# SCH_ShieldV1_1_sch_2022-06-14.net
KiCad netlist of a schematic drawn in EasyEDA
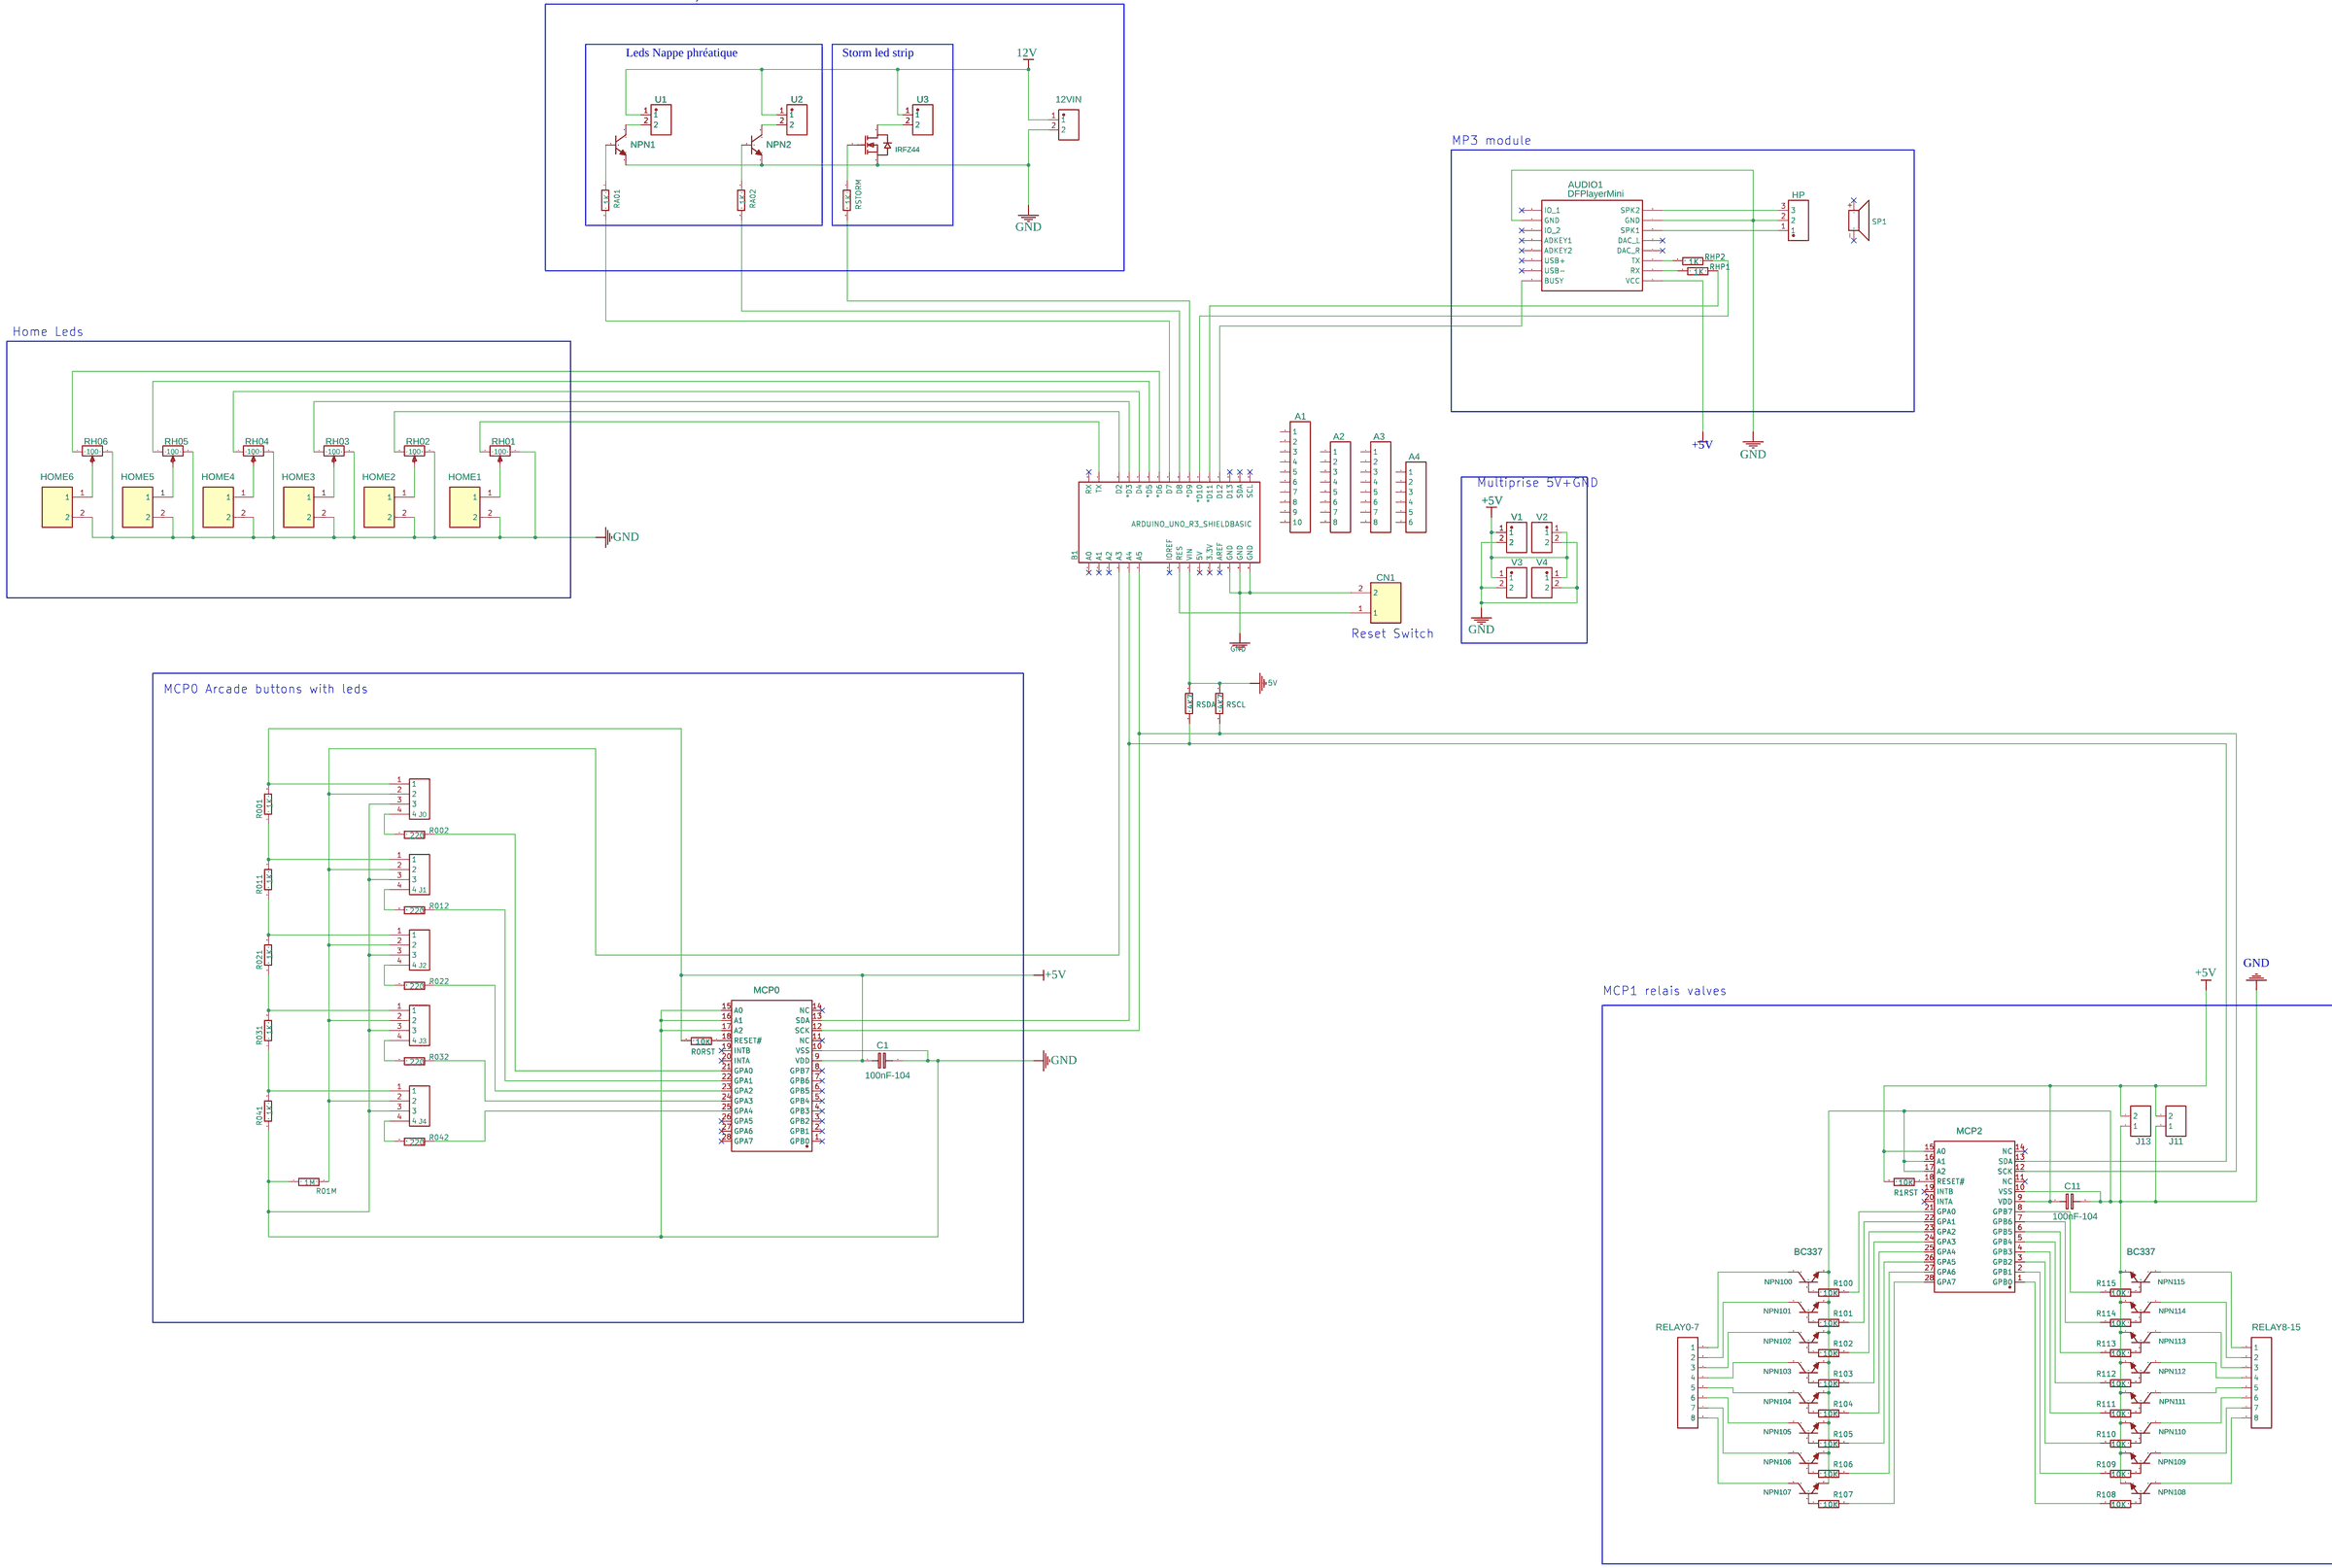
[diagram p0: Main board]
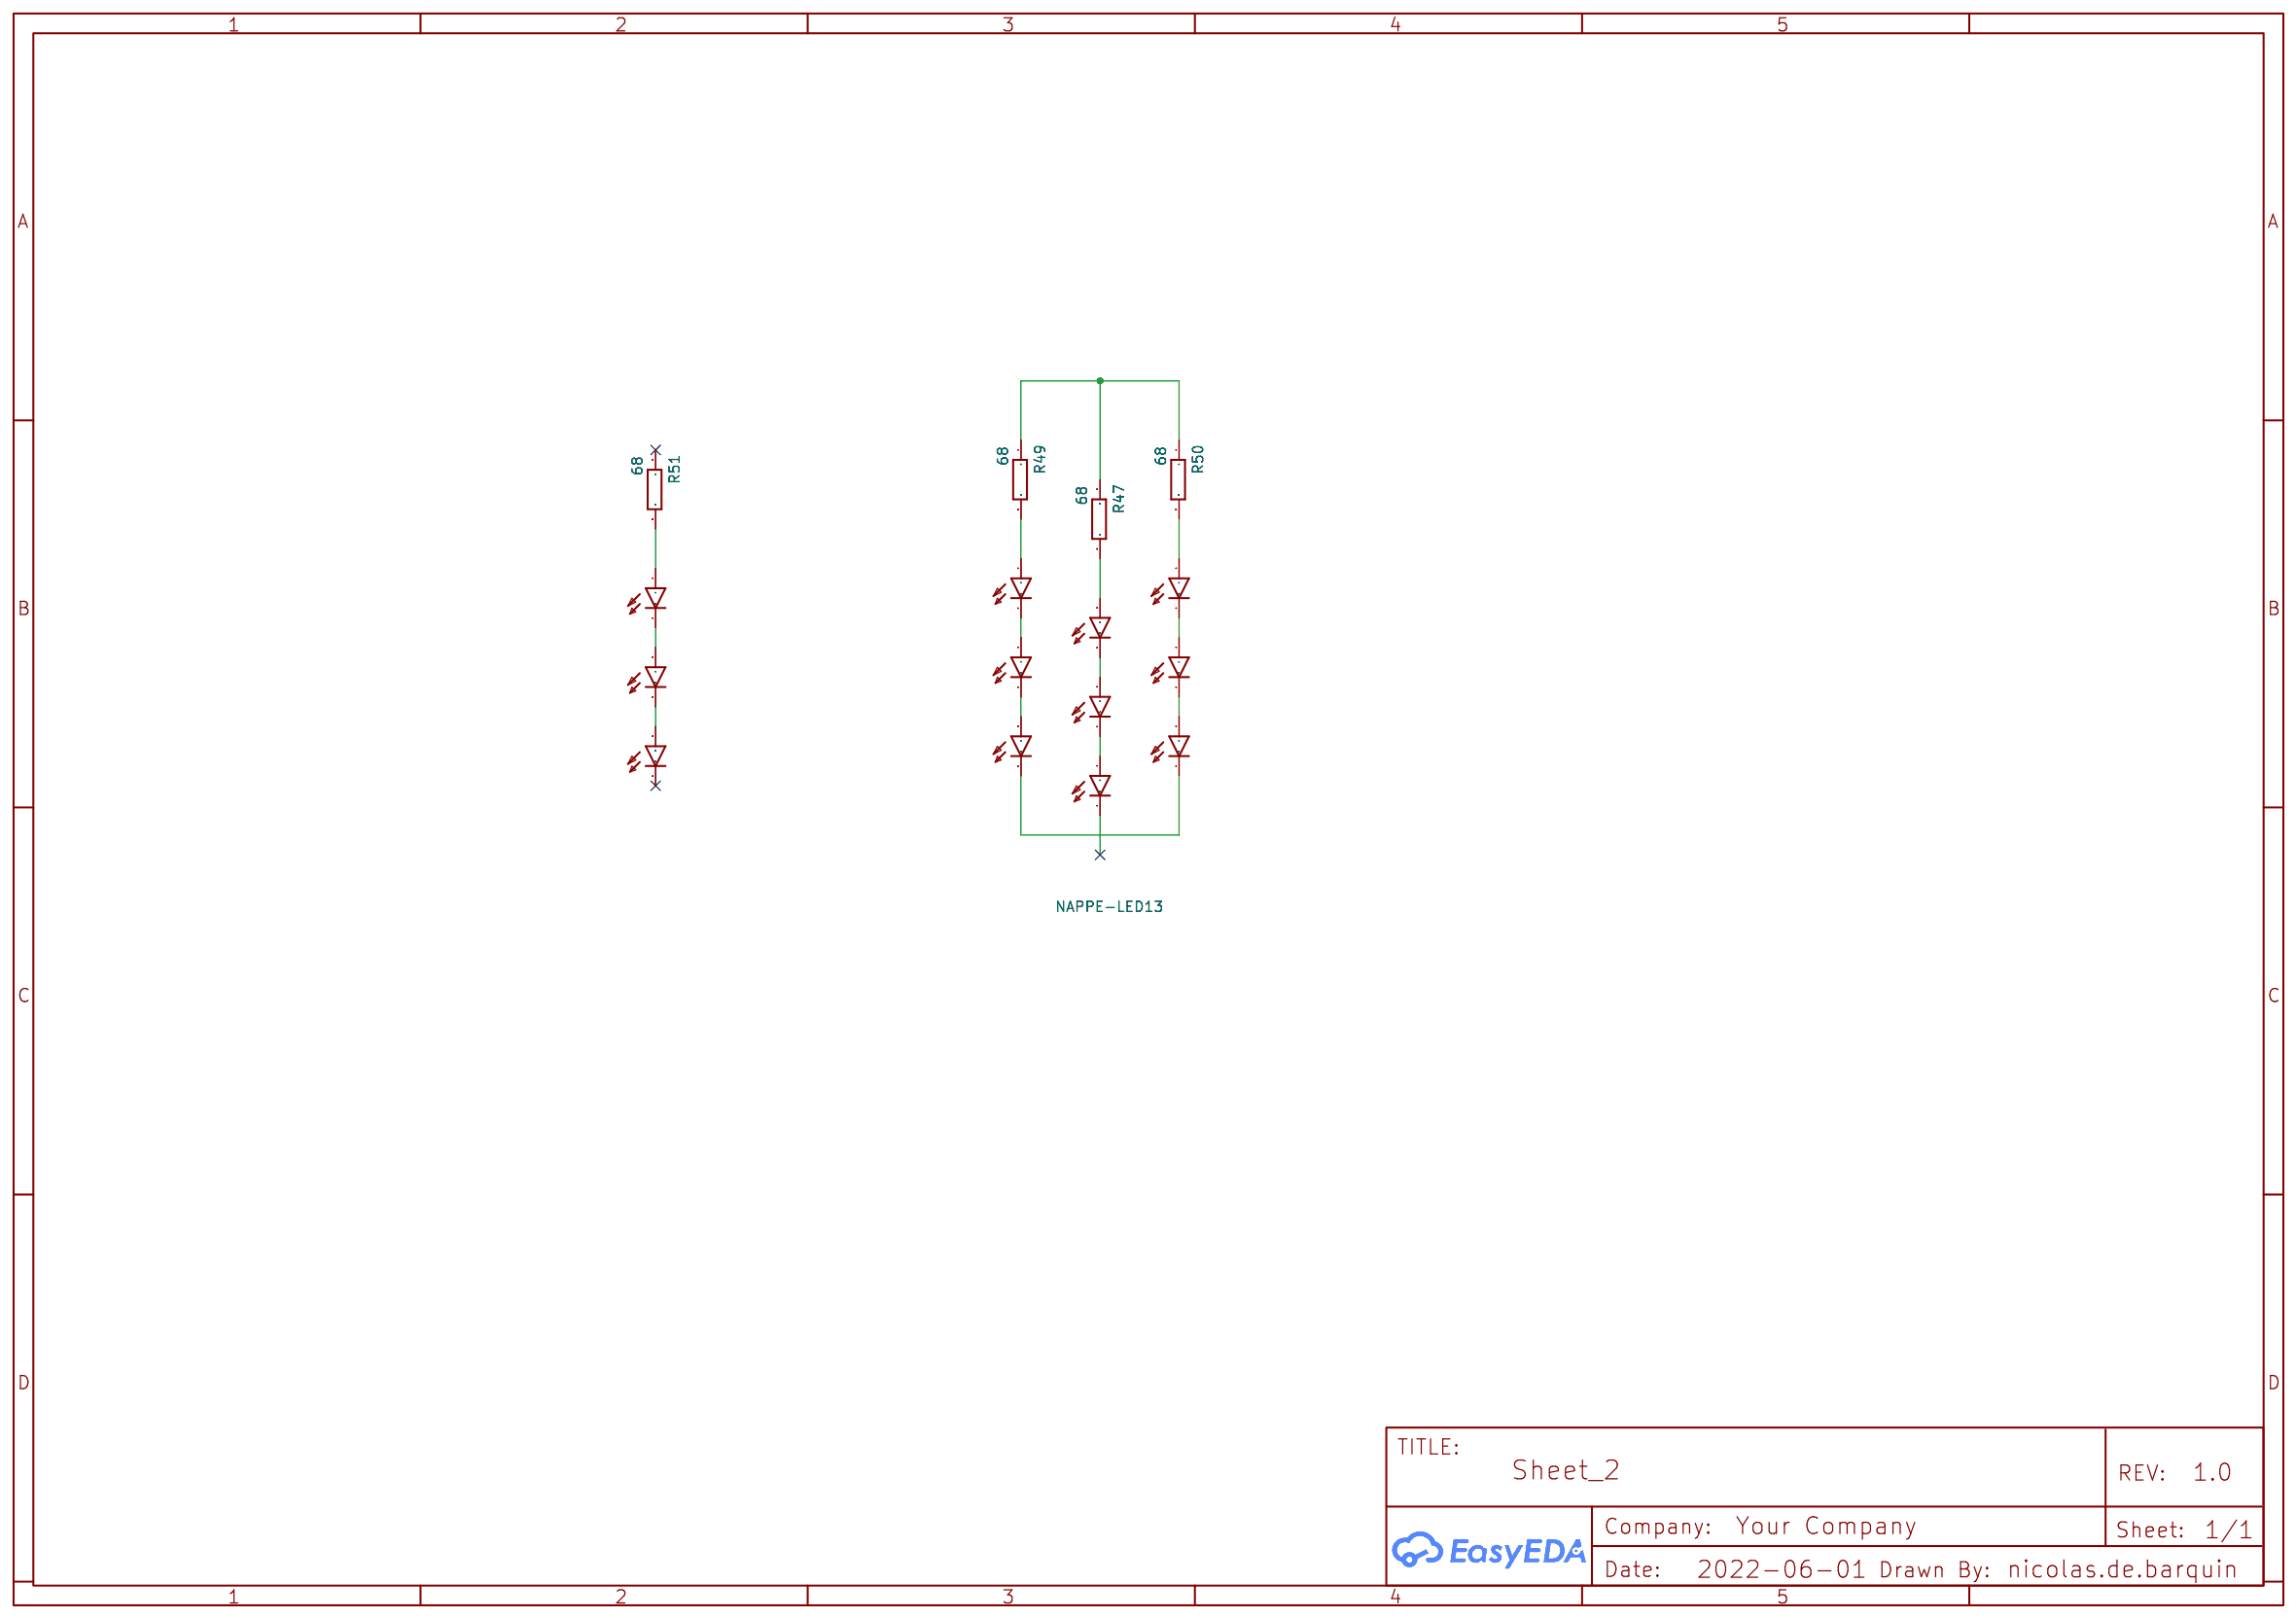
[diagram p1: leds]

(export (version "E")
  (design (tool "Eeschema 10.0.6"))
  (components
    (comp (ref "12VIN")
      (value "12V IN")
      (fields
        (field (name "BOM_Manufacturer Part") "KF301-5.0-2P")
        (field (name "BOM_Supplier Part") "C474881")
      )
      (libsource (lib "") (part "KF301-5.0-2P_3"))
    )
    (comp (ref "A1")
      (value "HDR-M-2.54_1x10")
      (fields (field (name "BOM_Supplier Part") "C57369"))
      (libsource (lib "") (part "HDR-M-2.54_1x10"))
    )
    (comp (ref "A2")
      (value "HDR-M-2.54_1x8")
      (fields (field (name "BOM_Supplier Part") "C190820"))
      (libsource (lib "") (part "HDR-M-2.54_1x8"))
    )
    (comp (ref "A3")
      (value "HDR-M-2.54_1x8")
      (fields (field (name "BOM_Supplier Part") "C190820"))
      (libsource (lib "") (part "HDR-M-2.54_1x8"))
    )
    (comp (ref "A4")
      (value "HDR-M-2.54_1x6")
      (fields (field (name "BOM_Supplier Part") "C190819"))
      (libsource (lib "") (part "HDR-M-2.54_1x6"))
    )
    (comp (ref "AUDIO1")
      (value "DFPlayerMini")
      (fields (field (name "BOM_Manufacturer Part") "DFPlayer mini"))
      (libsource (lib "") (part "DFPlayerMini"))
    )
    (comp (ref "B1") (value "ARDUINO_UNO_R3_SHIELDBASIC") (libsource (lib "") (part "Unknown_1660_-1370")))
    (comp (ref "C1") (value "100nF-104") (libsource (lib "") (part "C_RAD-0.1_EU")))
    (comp (ref "C11") (value "100nF-104") (libsource (lib "") (part "C_RAD-0.1_EU_1")))
    (comp (ref "CN1")
      (value "B2B-PH-K-S(LF)(SN)")
      (fields (field (name "BOM_Supplier Part") "C131337"))
      (libsource (lib "") (part "B2B-PH-K-S(LF)(SN)_1"))
    )
    (comp (ref "HOME1")
      (value "B2B-PH-K-S(LF)(SN)")
      (fields (field (name "BOM_Supplier Part") "C131337"))
      (libsource (lib "") (part "B2B-PH-K-S(LF)(SN)"))
    )
    (comp (ref "HOME2")
      (value "B2B-PH-K-S(LF)(SN)")
      (fields (field (name "BOM_Supplier Part") "C131337"))
      (libsource (lib "") (part "B2B-PH-K-S(LF)(SN)"))
    )
    (comp (ref "HOME3")
      (value "B2B-PH-K-S(LF)(SN)")
      (fields (field (name "BOM_Supplier Part") "C131337"))
      (libsource (lib "") (part "B2B-PH-K-S(LF)(SN)"))
    )
    (comp (ref "HOME4")
      (value "B2B-PH-K-S(LF)(SN)")
      (fields (field (name "BOM_Supplier Part") "C131337"))
      (libsource (lib "") (part "B2B-PH-K-S(LF)(SN)"))
    )
    (comp (ref "HOME5")
      (value "B2B-PH-K-S(LF)(SN)")
      (fields (field (name "BOM_Supplier Part") "C131337"))
      (libsource (lib "") (part "B2B-PH-K-S(LF)(SN)"))
    )
    (comp (ref "HOME6")
      (value "B2B-PH-K-S(LF)(SN)")
      (fields (field (name "BOM_Supplier Part") "C131337"))
      (libsource (lib "") (part "B2B-PH-K-S(LF)(SN)"))
    )
    (comp (ref "HP")
      (value "JL300-50003U01")
      (fields (field (name "BOM_Supplier Part") "C394552"))
      (libsource (lib "") (part "JL300-50003U01"))
    )
    (comp (ref "IRFZ44")
      (value "IRFZ44NPBF")
      (fields (field (name "BOM_Supplier Part") "C2586"))
      (libsource (lib "") (part "IRFZ44NPBF"))
    )
    (comp (ref "J0")
      (value "XHB-4A(White)/4needle")
      (fields (field (name "BOM_Supplier Part") "C61277"))
      (libsource (lib "") (part "XHB-4A(White)/4needle"))
    )
    (comp (ref "J1")
      (value "XHB-4A(White)/4needle")
      (fields (field (name "BOM_Supplier Part") "C61277"))
      (libsource (lib "") (part "XHB-4A(White)/4needle"))
    )
    (comp (ref "J2")
      (value "XHB-4A(White)/4needle")
      (fields (field (name "BOM_Supplier Part") "C61277"))
      (libsource (lib "") (part "XHB-4A(White)/4needle"))
    )
    (comp (ref "J3")
      (value "XHB-4A(White)/4needle")
      (fields (field (name "BOM_Supplier Part") "C61277"))
      (libsource (lib "") (part "XHB-4A(White)/4needle"))
    )
    (comp (ref "J4")
      (value "XHB-4A(White)/4needle")
      (fields (field (name "BOM_Supplier Part") "C61277"))
      (libsource (lib "") (part "XHB-4A(White)/4needle"))
    )
    (comp (ref "J11")
      (value "HDR-M-2.54_1x2")
      (fields (field (name "BOM_Supplier Part") "C124375"))
      (libsource (lib "") (part "HDR-M-2.54_1x2"))
    )
    (comp (ref "J13")
      (value "HDR-M-2.54_1x2")
      (fields (field (name "BOM_Supplier Part") "C124375"))
      (libsource (lib "") (part "HDR-M-2.54_1x2"))
    )
    (comp (ref "MCP0")
      (value "MCP23017-E/SP")
      (fields (field (name "BOM_Supplier Part") "C647352"))
      (libsource (lib "") (part "MCP23017-E/SP"))
    )
    (comp (ref "MCP2")
      (value "MCP23017-E/SP")
      (fields (field (name "BOM_Supplier Part") "C647352"))
      (libsource (lib "") (part "MCP23017-E/SP"))
    )
    (comp (ref "NPN1")
      (value "2N4401_C15986")
      (fields (field (name "BOM_Manufacturer Part") "2N4401") (field (name "BOM_Supplier Part") "C15986"))
      (libsource (lib "") (part "2N4401_C15986"))
    )
    (comp (ref "NPN2")
      (value "2N4401_C15986")
      (fields (field (name "BOM_Manufacturer Part") "2N4401") (field (name "BOM_Supplier Part") "C15986"))
      (libsource (lib "") (part "2N4401_C15986"))
    )
    (comp (ref "NPN100")
      (value "BC337")
      (fields (field (name "BOM_Manufacturer Part") "BC337-16") (field (name "BOM_Supplier Part") "C713609"))
      (libsource (lib "") (part "BC337-16"))
    )
    (comp (ref "NPN101")
      (value "BC337")
      (fields (field (name "BOM_Manufacturer Part") "BC337-16") (field (name "BOM_Supplier Part") "C713609"))
      (libsource (lib "") (part "BC337-16"))
    )
    (comp (ref "NPN102")
      (value "BC337")
      (fields (field (name "BOM_Manufacturer Part") "BC337-16") (field (name "BOM_Supplier Part") "C713609"))
      (libsource (lib "") (part "BC337-16"))
    )
    (comp (ref "NPN103")
      (value "BC337")
      (fields (field (name "BOM_Manufacturer Part") "BC337-16") (field (name "BOM_Supplier Part") "C713609"))
      (libsource (lib "") (part "BC337-16"))
    )
    (comp (ref "NPN104")
      (value "BC337")
      (fields (field (name "BOM_Manufacturer Part") "BC337-16") (field (name "BOM_Supplier Part") "C713609"))
      (libsource (lib "") (part "BC337-16"))
    )
    (comp (ref "NPN105")
      (value "BC337")
      (fields (field (name "BOM_Manufacturer Part") "BC337-16") (field (name "BOM_Supplier Part") "C713609"))
      (libsource (lib "") (part "BC337-16"))
    )
    (comp (ref "NPN106")
      (value "BC337")
      (fields (field (name "BOM_Manufacturer Part") "BC337-16") (field (name "BOM_Supplier Part") "C713609"))
      (libsource (lib "") (part "BC337-16"))
    )
    (comp (ref "NPN107")
      (value "BC337")
      (fields (field (name "BOM_Manufacturer Part") "BC337-16") (field (name "BOM_Supplier Part") "C713609"))
      (libsource (lib "") (part "BC337-16"))
    )
    (comp (ref "NPN108")
      (value "BC337")
      (fields (field (name "BOM_Manufacturer Part") "BC337-16") (field (name "BOM_Supplier Part") "C713609"))
      (libsource (lib "") (part "BC337-16_1"))
    )
    (comp (ref "NPN109")
      (value "BC337")
      (fields (field (name "BOM_Manufacturer Part") "BC337-16") (field (name "BOM_Supplier Part") "C713609"))
      (libsource (lib "") (part "BC337-16_1"))
    )
    (comp (ref "NPN110")
      (value "BC337")
      (fields (field (name "BOM_Manufacturer Part") "BC337-16") (field (name "BOM_Supplier Part") "C713609"))
      (libsource (lib "") (part "BC337-16_1"))
    )
    (comp (ref "NPN111")
      (value "BC337")
      (fields (field (name "BOM_Manufacturer Part") "BC337-16") (field (name "BOM_Supplier Part") "C713609"))
      (libsource (lib "") (part "BC337-16_1"))
    )
    (comp (ref "NPN112")
      (value "BC337")
      (fields (field (name "BOM_Manufacturer Part") "BC337-16") (field (name "BOM_Supplier Part") "C713609"))
      (libsource (lib "") (part "BC337-16_1"))
    )
    (comp (ref "NPN113")
      (value "BC337")
      (fields (field (name "BOM_Manufacturer Part") "BC337-16") (field (name "BOM_Supplier Part") "C713609"))
      (libsource (lib "") (part "BC337-16_1"))
    )
    (comp (ref "NPN114")
      (value "BC337")
      (fields (field (name "BOM_Manufacturer Part") "BC337-16") (field (name "BOM_Supplier Part") "C713609"))
      (libsource (lib "") (part "BC337-16_1"))
    )
    (comp (ref "NPN115")
      (value "BC337")
      (fields (field (name "BOM_Manufacturer Part") "BC337-16") (field (name "BOM_Supplier Part") "C713609"))
      (libsource (lib "") (part "BC337-16_1"))
    )
    (comp (ref "R0RST") (value "10K") (libsource (lib "") (part "Unknown_1205_-855")))
    (comp (ref "R001") (value "1K") (libsource (lib "") (part "Unknown_775_-1090")))
    (comp (ref "R01M") (value "1M") (libsource (lib "") (part "Unknown_815_-715")))
    (comp (ref "R1RST") (value "10K") (libsource (lib "") (part "Unknown_2400_-715")))
    (comp (ref "R002") (value "220") (libsource (lib "") (part "Unknown_920_-1060")))
    (comp (ref "R011") (value "1K") (libsource (lib "") (part "Unknown_775_-1015")))
    (comp (ref "R012") (value "220") (libsource (lib "") (part "Unknown_920_-985")))
    (comp (ref "R021") (value "1K") (libsource (lib "") (part "Unknown_775_-940")))
    (comp (ref "R022") (value "220") (libsource (lib "") (part "Unknown_920_-910")))
    (comp (ref "R031") (value "1K") (libsource (lib "") (part "Unknown_775_-865")))
    (comp (ref "R032") (value "220") (libsource (lib "") (part "Unknown_920_-835")))
    (comp (ref "R041") (value "1K") (libsource (lib "") (part "Unknown_775_-785")))
    (comp (ref "R042") (value "220") (libsource (lib "") (part "Unknown_920_-755")))
    (comp (ref "R100") (value "10K") (libsource (lib "") (part "Unknown_2325_-605")))
    (comp (ref "R101") (value "10K") (libsource (lib "") (part "Unknown_2325_-575")))
    (comp (ref "R102") (value "10K") (libsource (lib "") (part "Unknown_2325_-545")))
    (comp (ref "R103") (value "10K") (libsource (lib "") (part "Unknown_2325_-515")))
    (comp (ref "R104") (value "10K") (libsource (lib "") (part "Unknown_2325_-485")))
    (comp (ref "R105") (value "10K") (libsource (lib "") (part "Unknown_2325_-455")))
    (comp (ref "R106") (value "10K") (libsource (lib "") (part "Unknown_2325_-425")))
    (comp (ref "R107") (value "10K") (libsource (lib "") (part "Unknown_2325_-395")))
    (comp (ref "R108") (value "10K") (libsource (lib "") (part "Unknown_2615_-395")))
    (comp (ref "R109") (value "10K") (libsource (lib "") (part "Unknown_2615_-425")))
    (comp (ref "R110") (value "10K") (libsource (lib "") (part "Unknown_2615_-455")))
    (comp (ref "R111") (value "10K") (libsource (lib "") (part "Unknown_2615_-485")))
    (comp (ref "R112") (value "10K") (libsource (lib "") (part "Unknown_2615_-515")))
    (comp (ref "R113") (value "10K") (libsource (lib "") (part "Unknown_2615_-545")))
    (comp (ref "R114") (value "10K") (libsource (lib "") (part "Unknown_2615_-575")))
    (comp (ref "R115") (value "10K") (libsource (lib "") (part "Unknown_2615_-605")))
    (comp (ref "RA01") (value "1K") (libsource (lib "") (part "Unknown_1110_-1690")))
    (comp (ref "RA02") (value "1K") (libsource (lib "") (part "Unknown_1245_-1690")))
    (comp (ref "RELAY0-7")
      (value "HDR-M-2.54_1x8")
      (fields (field (name "BOM_Supplier Part") "C190820"))
      (libsource (lib "") (part "HDR-M-2.54_1x8_1"))
    )
    (comp (ref "RELAY8-15")
      (value "HDR-M-2.54_1x8")
      (fields (field (name "BOM_Supplier Part") "C190820"))
      (libsource (lib "") (part "HDR-M-2.54_1x8_2"))
    )
    (comp (ref "RH01")
      (value "100")
      (fields
        (field (name "BOM_Manufacturer Part") "GF063P1-B101")
        (field (name "BOM_Supplier Part") "C128075")
      )
      (libsource (lib "") (part "GF063P1-B101"))
    )
    (comp (ref "RH02")
      (value "100")
      (fields
        (field (name "BOM_Manufacturer Part") "GF063P1-B101")
        (field (name "BOM_Supplier Part") "C128075")
      )
      (libsource (lib "") (part "GF063P1-B101"))
    )
    (comp (ref "RH03")
      (value "100")
      (fields
        (field (name "BOM_Manufacturer Part") "GF063P1-B101")
        (field (name "BOM_Supplier Part") "C128075")
      )
      (libsource (lib "") (part "GF063P1-B101"))
    )
    (comp (ref "RH04")
      (value "100")
      (fields
        (field (name "BOM_Manufacturer Part") "GF063P1-B101")
        (field (name "BOM_Supplier Part") "C128075")
      )
      (libsource (lib "") (part "GF063P1-B101"))
    )
    (comp (ref "RH05")
      (value "100")
      (fields
        (field (name "BOM_Manufacturer Part") "GF063P1-B101")
        (field (name "BOM_Supplier Part") "C128075")
      )
      (libsource (lib "") (part "GF063P1-B101"))
    )
    (comp (ref "RH06")
      (value "100")
      (fields
        (field (name "BOM_Manufacturer Part") "GF063P1-B101")
        (field (name "BOM_Supplier Part") "C128075")
      )
      (libsource (lib "") (part "GF063P1-B101"))
    )
    (comp (ref "RHP1") (value "1K") (libsource (lib "") (part "Unknown_2195_-1620")))
    (comp (ref "RHP2") (value "1K") (libsource (lib "") (part "Unknown_2190_-1630")))
    (comp (ref "RSCL") (value "4K7") (libsource (lib "") (part "Unknown_1720_-1190")))
    (comp (ref "RSDA") (value "4K7") (libsource (lib "") (part "Unknown_1690_-1190")))
    (comp (ref "RSTORM") (value "1K") (libsource (lib "") (part "Unknown_1350_-1690")))
    (comp (ref "SP1") (value "SMS-1308MS-2-R") (libsource (lib "") (part "Unknown_2350_-1670")))
    (comp (ref "U1")
      (value "KF301-5.0-2P")
      (fields (field (name "BOM_Supplier Part") "C474881"))
      (libsource (lib "") (part "KF301-5.0-2P"))
    )
    (comp (ref "U2")
      (value "KF301-5.0-2P")
      (fields (field (name "BOM_Supplier Part") "C474881"))
      (libsource (lib "") (part "KF301-5.0-2P"))
    )
    (comp (ref "U3")
      (value "KF301-5.0-2P")
      (fields (field (name "BOM_Supplier Part") "C474881"))
      (libsource (lib "") (part "KF301-5.0-2P"))
    )
    (comp (ref "V1")
      (value "12V IN")
      (fields
        (field (name "BOM_Manufacturer Part") "KF301-5.0-2P")
        (field (name "BOM_Supplier Part") "C474881")
      )
      (libsource (lib "") (part "KF301-5.0-2P_2"))
    )
    (comp (ref "V2")
      (value "12V IN")
      (fields
        (field (name "BOM_Manufacturer Part") "KF301-5.0-2P")
        (field (name "BOM_Supplier Part") "C474881")
      )
      (libsource (lib "") (part "KF301-5.0-2P_1"))
    )
    (comp (ref "V3")
      (value "12V IN")
      (fields
        (field (name "BOM_Manufacturer Part") "KF301-5.0-2P")
        (field (name "BOM_Supplier Part") "C474881")
      )
      (libsource (lib "") (part "KF301-5.0-2P_2"))
    )
    (comp (ref "V4")
      (value "12V IN")
      (fields
        (field (name "BOM_Manufacturer Part") "KF301-5.0-2P")
        (field (name "BOM_Supplier Part") "C474881")
      )
      (libsource (lib "") (part "KF301-5.0-2P_1"))
    )
    (comp (ref "NAPPE-LED1") (value "LED5MM") (libsource (lib "") (part "Unknown_550_-460")))
    (comp (ref "NAPPE-LED2") (value "LED5MM") (libsource (lib "") (part "Unknown_550_-500")))
    (comp (ref "NAPPE-LED3") (value "LED5MM") (libsource (lib "") (part "Unknown_510_-440")))
    (comp (ref "NAPPE-LED4") (value "LED5MM") (libsource (lib "") (part "Unknown_510_-480")))
    (comp (ref "NAPPE-LED5") (value "LED5MM") (libsource (lib "") (part "Unknown_510_-520")))
    (comp (ref "NAPPE-LED6") (value "LED5MM") (libsource (lib "") (part "Unknown_590_-440")))
    (comp (ref "NAPPE-LED7") (value "LED5MM") (libsource (lib "") (part "Unknown_590_-480")))
    (comp (ref "NAPPE-LED8") (value "LED5MM") (libsource (lib "") (part "Unknown_590_-520")))
    (comp (ref "NAPPE-LED9") (value "LED5MM") (libsource (lib "") (part "Unknown_325_-435")))
    (comp (ref "NAPPE-LED10") (value "LED5MM") (libsource (lib "") (part "Unknown_325_-475")))
    (comp (ref "NAPPE-LED11") (value "LED5MM") (libsource (lib "") (part "Unknown_325_-515")))
    (comp (ref "NAPPE-LED13") (value "LED5MM") (libsource (lib "") (part "Unknown_550_-420")))
    (comp (ref "R47") (value "68") (libsource (lib "") (part "Unknown_550_-550")))
    (comp (ref "R49") (value "68") (libsource (lib "") (part "Unknown_510_-570")))
    (comp (ref "R50") (value "68") (libsource (lib "") (part "Unknown_590_-570")))
    (comp (ref "R51") (value "68") (libsource (lib "") (part "Unknown_325_-565")))
  )
  (nets
    (net (code "1") (name "+5V") (class "Default")
      (node (ref "AUDIO1") (pin "1") (pinfunction "VCC_1") (pintype "unspecified"))
      (node (ref "B1") (pin "VIN") (pinfunction "VIN_VIN") (pintype "bidirectional"))
      (node (ref "C1") (pin "1") (pinfunction "1_1") (pintype "unspecified"))
      (node (ref "C11") (pin "1") (pinfunction "1_1") (pintype "unspecified"))
      (node (ref "J0") (pin "1") (pinfunction "1_1") (pintype "unspecified"))
      (node (ref "J11") (pin "2") (pinfunction "2_2") (pintype "unspecified"))
      (node (ref "J13") (pin "2") (pinfunction "2_2") (pintype "unspecified"))
      (node (ref "MCP0") (pin "9") (pinfunction "VDD_9") (pintype "unspecified"))
      (node (ref "MCP2") (pin "15") (pinfunction "A0_15") (pintype "unspecified"))
      (node (ref "MCP2") (pin "9") (pinfunction "VDD_9") (pintype "unspecified"))
      (node (ref "R001") (pin "2") (pinfunction "2_2") (pintype "bidirectional"))
      (node (ref "R0RST") (pin "2") (pinfunction "2_2") (pintype "bidirectional"))
      (node (ref "R1RST") (pin "2") (pinfunction "2_2") (pintype "bidirectional"))
      (node (ref "RSCL") (pin "1") (pinfunction "1_1") (pintype "bidirectional"))
      (node (ref "RSDA") (pin "1") (pinfunction "1_1") (pintype "bidirectional"))
      (node (ref "V1") (pin "1") (pinfunction "1_1") (pintype "unspecified"))
      (node (ref "V2") (pin "1") (pinfunction "1_1") (pintype "unspecified"))
      (node (ref "V3") (pin "1") (pinfunction "1_1") (pintype "unspecified"))
      (node (ref "V4") (pin "1") (pinfunction "1_1") (pintype "unspecified"))
    )
    (net (code "2") (name "12V") (class "Default")
      (node (ref "12VIN") (pin "1") (pinfunction "1_1") (pintype "unspecified"))
      (node (ref "U1") (pin "1") (pinfunction "1_1") (pintype "unspecified"))
      (node (ref "U2") (pin "1") (pinfunction "1_1") (pintype "unspecified"))
      (node (ref "U3") (pin "1") (pinfunction "1_1") (pintype "unspecified"))
    )
    (net (code "3") (name "GND") (class "Default")
      (node (ref "12VIN") (pin "2") (pinfunction "2_2") (pintype "unspecified"))
      (node (ref "AUDIO1") (pin "15") (pinfunction "GND_15") (pintype "unspecified"))
      (node (ref "AUDIO1") (pin "7") (pinfunction "GND_7") (pintype "unspecified"))
      (node (ref "B1") (pin "GND@0") (pinfunction "GND_GND@0") (pintype "bidirectional"))
      (node (ref "B1") (pin "GND@1") (pinfunction "GND_GND@1") (pintype "bidirectional"))
      (node (ref "B1") (pin "GND@2") (pinfunction "GND_GND@2") (pintype "bidirectional"))
      (node (ref "C1") (pin "2") (pinfunction "2_2") (pintype "unspecified"))
      (node (ref "C11") (pin "2") (pinfunction "2_2") (pintype "unspecified"))
      (node (ref "CN1") (pin "2") (pinfunction "2_2") (pintype "input"))
      (node (ref "HOME1") (pin "2") (pinfunction "2_2") (pintype "input"))
      (node (ref "HOME2") (pin "2") (pinfunction "2_2") (pintype "input"))
      (node (ref "HOME3") (pin "2") (pinfunction "2_2") (pintype "input"))
      (node (ref "HOME4") (pin "2") (pinfunction "2_2") (pintype "input"))
      (node (ref "HOME5") (pin "2") (pinfunction "2_2") (pintype "input"))
      (node (ref "HOME6") (pin "2") (pinfunction "2_2") (pintype "input"))
      (node (ref "HP") (pin "2") (pinfunction "2_2") (pintype "unspecified"))
      (node (ref "IRFZ44") (pin "3") (pinfunction "S_3") (pintype "unspecified"))
      (node (ref "J0") (pin "3") (pinfunction "3_3") (pintype "unspecified"))
      (node (ref "J1") (pin "3") (pinfunction "3_3") (pintype "unspecified"))
      (node (ref "J11") (pin "1") (pinfunction "1_1") (pintype "unspecified"))
      (node (ref "J13") (pin "1") (pinfunction "1_1") (pintype "unspecified"))
      (node (ref "J2") (pin "3") (pinfunction "3_3") (pintype "unspecified"))
      (node (ref "J3") (pin "3") (pinfunction "3_3") (pintype "unspecified"))
      (node (ref "J4") (pin "3") (pinfunction "3_3") (pintype "unspecified"))
      (node (ref "MCP0") (pin "10") (pinfunction "VSS_10") (pintype "unspecified"))
      (node (ref "MCP0") (pin "15") (pinfunction "A0_15") (pintype "unspecified"))
      (node (ref "MCP0") (pin "16") (pinfunction "A1_16") (pintype "unspecified"))
      (node (ref "MCP0") (pin "17") (pinfunction "A2_17") (pintype "unspecified"))
      (node (ref "MCP2") (pin "10") (pinfunction "VSS_10") (pintype "unspecified"))
      (node (ref "MCP2") (pin "16") (pinfunction "A1_16") (pintype "unspecified"))
      (node (ref "MCP2") (pin "17") (pinfunction "A2_17") (pintype "unspecified"))
      (node (ref "NPN1") (pin "1") (pinfunction "E_1") (pintype "unspecified"))
      (node (ref "NPN100") (pin "3") (pinfunction "E_3") (pintype "input"))
      (node (ref "NPN101") (pin "3") (pinfunction "E_3") (pintype "input"))
      (node (ref "NPN102") (pin "3") (pinfunction "E_3") (pintype "input"))
      (node (ref "NPN103") (pin "3") (pinfunction "E_3") (pintype "input"))
      (node (ref "NPN104") (pin "3") (pinfunction "E_3") (pintype "input"))
      (node (ref "NPN105") (pin "3") (pinfunction "E_3") (pintype "input"))
      (node (ref "NPN106") (pin "3") (pinfunction "E_3") (pintype "input"))
      (node (ref "NPN107") (pin "3") (pinfunction "E_3") (pintype "input"))
      (node (ref "NPN108") (pin "3") (pinfunction "E_3") (pintype "input"))
      (node (ref "NPN109") (pin "3") (pinfunction "E_3") (pintype "input"))
      (node (ref "NPN110") (pin "3") (pinfunction "E_3") (pintype "input"))
      (node (ref "NPN111") (pin "3") (pinfunction "E_3") (pintype "input"))
      (node (ref "NPN112") (pin "3") (pinfunction "E_3") (pintype "input"))
      (node (ref "NPN113") (pin "3") (pinfunction "E_3") (pintype "input"))
      (node (ref "NPN114") (pin "3") (pinfunction "E_3") (pintype "input"))
      (node (ref "NPN115") (pin "3") (pinfunction "E_3") (pintype "input"))
      (node (ref "NPN2") (pin "1") (pinfunction "E_1") (pintype "unspecified"))
      (node (ref "R01M") (pin "2") (pinfunction "2_2") (pintype "bidirectional"))
      (node (ref "R041") (pin "1") (pinfunction "1_1") (pintype "bidirectional"))
      (node (ref "RH01") (pin "3") (pinfunction "3_3") (pintype "input"))
      (node (ref "RH02") (pin "3") (pinfunction "3_3") (pintype "input"))
      (node (ref "RH03") (pin "3") (pinfunction "3_3") (pintype "input"))
      (node (ref "RH04") (pin "3") (pinfunction "3_3") (pintype "input"))
      (node (ref "RH05") (pin "3") (pinfunction "3_3") (pintype "input"))
      (node (ref "RH06") (pin "3") (pinfunction "3_3") (pintype "input"))
      (node (ref "V1") (pin "2") (pinfunction "2_2") (pintype "unspecified"))
      (node (ref "V2") (pin "2") (pinfunction "2_2") (pintype "unspecified"))
      (node (ref "V3") (pin "2") (pinfunction "2_2") (pintype "unspecified"))
      (node (ref "V4") (pin "2") (pinfunction "2_2") (pintype "unspecified"))
    )
    (net (code "4") (name "Net-(AUDIO1-BUSY)") (class "Default")
      (node (ref "AUDIO1") (pin "9") (pinfunction "BUSY_9") (pintype "unspecified"))
      (node (ref "B1") (pin "D12") (pinfunction "D12_D12") (pintype "bidirectional"))
    )
    (net (code "5") (name "Net-(AUDIO1-RX)") (class "Default")
      (node (ref "AUDIO1") (pin "2") (pinfunction "RX_2") (pintype "unspecified"))
      (node (ref "RHP1") (pin "2") (pinfunction "2_2") (pintype "bidirectional"))
    )
    (net (code "6") (name "Net-(AUDIO1-SPK1)") (class "Default")
      (node (ref "AUDIO1") (pin "6") (pinfunction "SPK1_6") (pintype "unspecified"))
      (node (ref "HP") (pin "1") (pinfunction "1_1") (pintype "unspecified"))
    )
    (net (code "7") (name "Net-(AUDIO1-SPK2)") (class "Default")
      (node (ref "AUDIO1") (pin "8") (pinfunction "SPK2_8") (pintype "unspecified"))
      (node (ref "HP") (pin "3") (pinfunction "3_3") (pintype "unspecified"))
    )
    (net (code "8") (name "Net-(AUDIO1-TX)") (class "Default")
      (node (ref "AUDIO1") (pin "3") (pinfunction "TX_3") (pintype "unspecified"))
      (node (ref "RHP2") (pin "1") (pinfunction "1_1") (pintype "bidirectional"))
    )
    (net (code "9") (name "Net-(B1-*D3)") (class "Default")
      (node (ref "B1") (pin "D3") (pinfunction "*D3_D3") (pintype "bidirectional"))
      (node (ref "RH03") (pin "1") (pinfunction "1_1") (pintype "input"))
    )
    (net (code "10") (name "Net-(B1-*D5)") (class "Default")
      (node (ref "B1") (pin "D5") (pinfunction "*D5_D5") (pintype "bidirectional"))
      (node (ref "RH05") (pin "1") (pinfunction "1_1") (pintype "input"))
    )
    (net (code "11") (name "Net-(B1-*D6)") (class "Default")
      (node (ref "B1") (pin "D6") (pinfunction "*D6_D6") (pintype "bidirectional"))
      (node (ref "RH06") (pin "1") (pinfunction "1_1") (pintype "input"))
    )
    (net (code "12") (name "Net-(B1-*D9)") (class "Default")
      (node (ref "B1") (pin "D9") (pinfunction "*D9_D9") (pintype "bidirectional"))
      (node (ref "RSTORM") (pin "2") (pinfunction "2_2") (pintype "bidirectional"))
    )
    (net (code "13") (name "Net-(B1-*D10)") (class "Default")
      (node (ref "B1") (pin "D10") (pinfunction "*D10_D10") (pintype "bidirectional"))
      (node (ref "RHP2") (pin "2") (pinfunction "2_2") (pintype "bidirectional"))
    )
    (net (code "14") (name "Net-(B1-*D11)") (class "Default")
      (node (ref "B1") (pin "D11") (pinfunction "*D11_D11") (pintype "bidirectional"))
      (node (ref "RHP1") (pin "1") (pinfunction "1_1") (pintype "bidirectional"))
    )
    (net (code "15") (name "Net-(B1-PadA3)") (class "Default")
      (node (ref "B1") (pin "A3") (pinfunction "A3_A3") (pintype "bidirectional"))
      (node (ref "J0") (pin "2") (pinfunction "2_2") (pintype "unspecified"))
      (node (ref "J1") (pin "2") (pinfunction "2_2") (pintype "unspecified"))
      (node (ref "J2") (pin "2") (pinfunction "2_2") (pintype "unspecified"))
      (node (ref "J3") (pin "2") (pinfunction "2_2") (pintype "unspecified"))
      (node (ref "J4") (pin "2") (pinfunction "2_2") (pintype "unspecified"))
      (node (ref "R01M") (pin "1") (pinfunction "1_1") (pintype "bidirectional"))
    )
    (net (code "16") (name "Net-(B1-PadD2)") (class "Default")
      (node (ref "B1") (pin "D2") (pinfunction "D2_D2") (pintype "bidirectional"))
      (node (ref "RH02") (pin "1") (pinfunction "1_1") (pintype "input"))
    )
    (net (code "17") (name "Net-(B1-PadD4)") (class "Default")
      (node (ref "B1") (pin "D4") (pinfunction "D4_D4") (pintype "bidirectional"))
      (node (ref "RH04") (pin "1") (pinfunction "1_1") (pintype "input"))
    )
    (net (code "18") (name "Net-(B1-PadD7)") (class "Default")
      (node (ref "B1") (pin "D7") (pinfunction "D7_D7") (pintype "bidirectional"))
      (node (ref "RA01") (pin "2") (pinfunction "2_2") (pintype "bidirectional"))
    )
    (net (code "19") (name "Net-(B1-PadD8)") (class "Default")
      (node (ref "B1") (pin "D8") (pinfunction "D8_D8") (pintype "bidirectional"))
      (node (ref "RA02") (pin "2") (pinfunction "2_2") (pintype "bidirectional"))
    )
    (net (code "20") (name "Net-(B1-PadRES)") (class "Default")
      (node (ref "B1") (pin "RES") (pinfunction "RES_RES") (pintype "bidirectional"))
      (node (ref "CN1") (pin "1") (pinfunction "1_1") (pintype "input"))
    )
    (net (code "21") (name "Net-(B1-PadTX)") (class "Default")
      (node (ref "B1") (pin "TX") (pinfunction "TX_TX") (pintype "bidirectional"))
      (node (ref "RH01") (pin "1") (pinfunction "1_1") (pintype "input"))
    )
    (net (code "22") (name "Net-(HOME1-Pad1)") (class "Default")
      (node (ref "HOME1") (pin "1") (pinfunction "1_1") (pintype "input"))
      (node (ref "RH01") (pin "2") (pinfunction "2_2") (pintype "input"))
    )
    (net (code "23") (name "Net-(HOME2-Pad1)") (class "Default")
      (node (ref "HOME2") (pin "1") (pinfunction "1_1") (pintype "input"))
      (node (ref "RH02") (pin "2") (pinfunction "2_2") (pintype "input"))
    )
    (net (code "24") (name "Net-(HOME3-Pad1)") (class "Default")
      (node (ref "HOME3") (pin "1") (pinfunction "1_1") (pintype "input"))
      (node (ref "RH03") (pin "2") (pinfunction "2_2") (pintype "input"))
    )
    (net (code "25") (name "Net-(HOME4-Pad1)") (class "Default")
      (node (ref "HOME4") (pin "1") (pinfunction "1_1") (pintype "input"))
      (node (ref "RH04") (pin "2") (pinfunction "2_2") (pintype "input"))
    )
    (net (code "26") (name "Net-(HOME5-Pad1)") (class "Default")
      (node (ref "HOME5") (pin "1") (pinfunction "1_1") (pintype "input"))
      (node (ref "RH05") (pin "2") (pinfunction "2_2") (pintype "input"))
    )
    (net (code "27") (name "Net-(HOME6-Pad1)") (class "Default")
      (node (ref "HOME6") (pin "1") (pinfunction "1_1") (pintype "input"))
      (node (ref "RH06") (pin "2") (pinfunction "2_2") (pintype "input"))
    )
    (net (code "28") (name "Net-(IRFZ44-D)") (class "Default")
      (node (ref "IRFZ44") (pin "2") (pinfunction "D_2") (pintype "unspecified"))
      (node (ref "U3") (pin "2") (pinfunction "2_2") (pintype "unspecified"))
    )
    (net (code "29") (name "Net-(IRFZ44-G)") (class "Default")
      (node (ref "IRFZ44") (pin "1") (pinfunction "G_1") (pintype "unspecified"))
      (node (ref "RSTORM") (pin "1") (pinfunction "1_1") (pintype "bidirectional"))
    )
    (net (code "30") (name "Net-(J0-Pad4)") (class "Default")
      (node (ref "J0") (pin "4") (pinfunction "4_4") (pintype "unspecified"))
      (node (ref "R002") (pin "2") (pinfunction "2_2") (pintype "bidirectional"))
    )
    (net (code "31") (name "Net-(J1-Pad1)") (class "Default")
      (node (ref "J1") (pin "1") (pinfunction "1_1") (pintype "unspecified"))
      (node (ref "R001") (pin "1") (pinfunction "1_1") (pintype "bidirectional"))
      (node (ref "R011") (pin "2") (pinfunction "2_2") (pintype "bidirectional"))
    )
    (net (code "32") (name "Net-(J1-Pad4)") (class "Default")
      (node (ref "J1") (pin "4") (pinfunction "4_4") (pintype "unspecified"))
      (node (ref "R012") (pin "2") (pinfunction "2_2") (pintype "bidirectional"))
    )
    (net (code "33") (name "Net-(J2-Pad1)") (class "Default")
      (node (ref "J2") (pin "1") (pinfunction "1_1") (pintype "unspecified"))
      (node (ref "R011") (pin "1") (pinfunction "1_1") (pintype "bidirectional"))
      (node (ref "R021") (pin "2") (pinfunction "2_2") (pintype "bidirectional"))
    )
    (net (code "34") (name "Net-(J2-Pad4)") (class "Default")
      (node (ref "J2") (pin "4") (pinfunction "4_4") (pintype "unspecified"))
      (node (ref "R022") (pin "2") (pinfunction "2_2") (pintype "bidirectional"))
    )
    (net (code "35") (name "Net-(J3-Pad1)") (class "Default")
      (node (ref "J3") (pin "1") (pinfunction "1_1") (pintype "unspecified"))
      (node (ref "R021") (pin "1") (pinfunction "1_1") (pintype "bidirectional"))
      (node (ref "R031") (pin "2") (pinfunction "2_2") (pintype "bidirectional"))
    )
    (net (code "36") (name "Net-(J3-Pad4)") (class "Default")
      (node (ref "J3") (pin "4") (pinfunction "4_4") (pintype "unspecified"))
      (node (ref "R032") (pin "2") (pinfunction "2_2") (pintype "bidirectional"))
    )
    (net (code "37") (name "Net-(J4-Pad1)") (class "Default")
      (node (ref "J4") (pin "1") (pinfunction "1_1") (pintype "unspecified"))
      (node (ref "R031") (pin "1") (pinfunction "1_1") (pintype "bidirectional"))
      (node (ref "R041") (pin "2") (pinfunction "2_2") (pintype "bidirectional"))
    )
    (net (code "38") (name "Net-(J4-Pad4)") (class "Default")
      (node (ref "J4") (pin "4") (pinfunction "4_4") (pintype "unspecified"))
      (node (ref "R042") (pin "2") (pinfunction "2_2") (pintype "bidirectional"))
    )
    (net (code "39") (name "Net-(MCP0-GPA0)") (class "Default")
      (node (ref "MCP0") (pin "21") (pinfunction "GPA0_21") (pintype "unspecified"))
      (node (ref "R002") (pin "1") (pinfunction "1_1") (pintype "bidirectional"))
    )
    (net (code "40") (name "Net-(MCP0-GPA1)") (class "Default")
      (node (ref "MCP0") (pin "22") (pinfunction "GPA1_22") (pintype "unspecified"))
      (node (ref "R012") (pin "1") (pinfunction "1_1") (pintype "bidirectional"))
    )
    (net (code "41") (name "Net-(MCP0-GPA2)") (class "Default")
      (node (ref "MCP0") (pin "23") (pinfunction "GPA2_23") (pintype "unspecified"))
      (node (ref "R022") (pin "1") (pinfunction "1_1") (pintype "bidirectional"))
    )
    (net (code "42") (name "Net-(MCP0-GPA3)") (class "Default")
      (node (ref "MCP0") (pin "24") (pinfunction "GPA3_24") (pintype "unspecified"))
      (node (ref "R032") (pin "1") (pinfunction "1_1") (pintype "bidirectional"))
    )
    (net (code "43") (name "Net-(MCP0-GPA4)") (class "Default")
      (node (ref "MCP0") (pin "25") (pinfunction "GPA4_25") (pintype "unspecified"))
      (node (ref "R042") (pin "1") (pinfunction "1_1") (pintype "bidirectional"))
    )
    (net (code "44") (name "Net-(MCP0-RESET#)") (class "Default")
      (node (ref "MCP0") (pin "18") (pinfunction "RESET#_18") (pintype "unspecified"))
      (node (ref "R0RST") (pin "1") (pinfunction "1_1") (pintype "bidirectional"))
    )
    (net (code "45") (name "Net-(MCP0-SCK)") (class "Default")
      (node (ref "B1") (pin "A5") (pinfunction "A5_A5") (pintype "bidirectional"))
      (node (ref "MCP0") (pin "12") (pinfunction "SCK_12") (pintype "unspecified"))
      (node (ref "MCP2") (pin "12") (pinfunction "SCK_12") (pintype "unspecified"))
      (node (ref "RSCL") (pin "2") (pinfunction "2_2") (pintype "bidirectional"))
    )
    (net (code "46") (name "Net-(MCP0-SDA)") (class "Default")
      (node (ref "B1") (pin "A4") (pinfunction "A4_A4") (pintype "bidirectional"))
      (node (ref "MCP0") (pin "13") (pinfunction "SDA_13") (pintype "unspecified"))
      (node (ref "MCP2") (pin "13") (pinfunction "SDA_13") (pintype "unspecified"))
      (node (ref "RSDA") (pin "2") (pinfunction "2_2") (pintype "bidirectional"))
    )
    (net (code "47") (name "Net-(MCP2-GPA0)") (class "Default")
      (node (ref "MCP2") (pin "21") (pinfunction "GPA0_21") (pintype "unspecified"))
      (node (ref "R100") (pin "2") (pinfunction "2_2") (pintype "bidirectional"))
    )
    (net (code "48") (name "Net-(MCP2-GPA1)") (class "Default")
      (node (ref "MCP2") (pin "22") (pinfunction "GPA1_22") (pintype "unspecified"))
      (node (ref "R101") (pin "2") (pinfunction "2_2") (pintype "bidirectional"))
    )
    (net (code "49") (name "Net-(MCP2-GPA2)") (class "Default")
      (node (ref "MCP2") (pin "23") (pinfunction "GPA2_23") (pintype "unspecified"))
      (node (ref "R102") (pin "2") (pinfunction "2_2") (pintype "bidirectional"))
    )
    (net (code "50") (name "Net-(MCP2-GPA3)") (class "Default")
      (node (ref "MCP2") (pin "24") (pinfunction "GPA3_24") (pintype "unspecified"))
      (node (ref "R103") (pin "2") (pinfunction "2_2") (pintype "bidirectional"))
    )
    (net (code "51") (name "Net-(MCP2-GPA4)") (class "Default")
      (node (ref "MCP2") (pin "25") (pinfunction "GPA4_25") (pintype "unspecified"))
      (node (ref "R104") (pin "2") (pinfunction "2_2") (pintype "bidirectional"))
    )
    (net (code "52") (name "Net-(MCP2-GPA5)") (class "Default")
      (node (ref "MCP2") (pin "26") (pinfunction "GPA5_26") (pintype "unspecified"))
      (node (ref "R105") (pin "2") (pinfunction "2_2") (pintype "bidirectional"))
    )
    (net (code "53") (name "Net-(MCP2-GPA6)") (class "Default")
      (node (ref "MCP2") (pin "27") (pinfunction "GPA6_27") (pintype "unspecified"))
      (node (ref "R106") (pin "2") (pinfunction "2_2") (pintype "bidirectional"))
    )
    (net (code "54") (name "Net-(MCP2-GPA7)") (class "Default")
      (node (ref "MCP2") (pin "28") (pinfunction "GPA7_28") (pintype "unspecified"))
      (node (ref "R107") (pin "2") (pinfunction "2_2") (pintype "bidirectional"))
    )
    (net (code "55") (name "Net-(MCP2-GPB0)") (class "Default")
      (node (ref "MCP2") (pin "1") (pinfunction "GPB0_1") (pintype "unspecified"))
      (node (ref "R108") (pin "2") (pinfunction "2_2") (pintype "bidirectional"))
    )
    (net (code "56") (name "Net-(MCP2-GPB1)") (class "Default")
      (node (ref "MCP2") (pin "2") (pinfunction "GPB1_2") (pintype "unspecified"))
      (node (ref "R109") (pin "2") (pinfunction "2_2") (pintype "bidirectional"))
    )
    (net (code "57") (name "Net-(MCP2-GPB2)") (class "Default")
      (node (ref "MCP2") (pin "3") (pinfunction "GPB2_3") (pintype "unspecified"))
      (node (ref "R110") (pin "2") (pinfunction "2_2") (pintype "bidirectional"))
    )
    (net (code "58") (name "Net-(MCP2-GPB3)") (class "Default")
      (node (ref "MCP2") (pin "4") (pinfunction "GPB3_4") (pintype "unspecified"))
      (node (ref "R111") (pin "2") (pinfunction "2_2") (pintype "bidirectional"))
    )
    (net (code "59") (name "Net-(MCP2-GPB4)") (class "Default")
      (node (ref "MCP2") (pin "5") (pinfunction "GPB4_5") (pintype "unspecified"))
      (node (ref "R112") (pin "2") (pinfunction "2_2") (pintype "bidirectional"))
    )
    (net (code "60") (name "Net-(MCP2-GPB5)") (class "Default")
      (node (ref "MCP2") (pin "6") (pinfunction "GPB5_6") (pintype "unspecified"))
      (node (ref "R113") (pin "2") (pinfunction "2_2") (pintype "bidirectional"))
    )
    (net (code "61") (name "Net-(MCP2-GPB6)") (class "Default")
      (node (ref "MCP2") (pin "7") (pinfunction "GPB6_7") (pintype "unspecified"))
      (node (ref "R114") (pin "2") (pinfunction "2_2") (pintype "bidirectional"))
    )
    (net (code "62") (name "Net-(MCP2-GPB7)") (class "Default")
      (node (ref "MCP2") (pin "8") (pinfunction "GPB7_8") (pintype "unspecified"))
      (node (ref "R115") (pin "2") (pinfunction "2_2") (pintype "bidirectional"))
    )
    (net (code "63") (name "Net-(MCP2-RESET#)") (class "Default")
      (node (ref "MCP2") (pin "18") (pinfunction "RESET#_18") (pintype "unspecified"))
      (node (ref "R1RST") (pin "1") (pinfunction "1_1") (pintype "bidirectional"))
    )
    (net (code "64") (name "Net-(NAPPE-LED1-C)") (class "Default")
      (node (ref "NAPPE-LED1") (pin "K") (pinfunction "C_K") (pintype "bidirectional"))
      (node (ref "NAPPE-LED13") (pin "A") (pinfunction "A_A") (pintype "bidirectional"))
    )
    (net (code "65") (name "Net-(NAPPE-LED2-C)") (class "Default")
      (node (ref "NAPPE-LED1") (pin "A") (pinfunction "A_A") (pintype "bidirectional"))
      (node (ref "NAPPE-LED2") (pin "K") (pinfunction "C_K") (pintype "bidirectional"))
    )
    (net (code "66") (name "Net-(NAPPE-LED2-PadA)") (class "Default")
      (node (ref "NAPPE-LED2") (pin "A") (pinfunction "A_A") (pintype "bidirectional"))
      (node (ref "R47") (pin "2") (pinfunction "2_2") (pintype "bidirectional"))
    )
    (net (code "67") (name "Net-(NAPPE-LED3-C)") (class "Default")
      (node (ref "NAPPE-LED3") (pin "K") (pinfunction "C_K") (pintype "bidirectional"))
      (node (ref "NAPPE-LED6") (pin "K") (pinfunction "C_K") (pintype "bidirectional"))
    )
    (net (code "68") (name "Net-(NAPPE-LED4-C)") (class "Default")
      (node (ref "NAPPE-LED3") (pin "A") (pinfunction "A_A") (pintype "bidirectional"))
      (node (ref "NAPPE-LED4") (pin "K") (pinfunction "C_K") (pintype "bidirectional"))
    )
    (net (code "69") (name "Net-(NAPPE-LED5-C)") (class "Default")
      (node (ref "NAPPE-LED4") (pin "A") (pinfunction "A_A") (pintype "bidirectional"))
      (node (ref "NAPPE-LED5") (pin "K") (pinfunction "C_K") (pintype "bidirectional"))
    )
    (net (code "70") (name "Net-(NAPPE-LED5-PadA)") (class "Default")
      (node (ref "NAPPE-LED5") (pin "A") (pinfunction "A_A") (pintype "bidirectional"))
      (node (ref "R49") (pin "2") (pinfunction "2_2") (pintype "bidirectional"))
    )
    (net (code "71") (name "Net-(NAPPE-LED7-C)") (class "Default")
      (node (ref "NAPPE-LED6") (pin "A") (pinfunction "A_A") (pintype "bidirectional"))
      (node (ref "NAPPE-LED7") (pin "K") (pinfunction "C_K") (pintype "bidirectional"))
    )
    (net (code "72") (name "Net-(NAPPE-LED8-C)") (class "Default")
      (node (ref "NAPPE-LED7") (pin "A") (pinfunction "A_A") (pintype "bidirectional"))
      (node (ref "NAPPE-LED8") (pin "K") (pinfunction "C_K") (pintype "bidirectional"))
    )
    (net (code "73") (name "Net-(NAPPE-LED8-PadA)") (class "Default")
      (node (ref "NAPPE-LED8") (pin "A") (pinfunction "A_A") (pintype "bidirectional"))
      (node (ref "R50") (pin "2") (pinfunction "2_2") (pintype "bidirectional"))
    )
    (net (code "74") (name "Net-(NAPPE-LED10-C)") (class "Default")
      (node (ref "NAPPE-LED10") (pin "K") (pinfunction "C_K") (pintype "bidirectional"))
      (node (ref "NAPPE-LED9") (pin "A") (pinfunction "A_A") (pintype "bidirectional"))
    )
    (net (code "75") (name "Net-(NAPPE-LED11-C)") (class "Default")
      (node (ref "NAPPE-LED10") (pin "A") (pinfunction "A_A") (pintype "bidirectional"))
      (node (ref "NAPPE-LED11") (pin "K") (pinfunction "C_K") (pintype "bidirectional"))
    )
    (net (code "76") (name "Net-(NAPPE-LED11-PadA)") (class "Default")
      (node (ref "NAPPE-LED11") (pin "A") (pinfunction "A_A") (pintype "bidirectional"))
      (node (ref "R51") (pin "2") (pinfunction "2_2") (pintype "bidirectional"))
    )
    (net (code "77") (name "Net-(NPN1-B)") (class "Default")
      (node (ref "NPN1") (pin "2") (pinfunction "B_2") (pintype "unspecified"))
      (node (ref "RA01") (pin "1") (pinfunction "1_1") (pintype "bidirectional"))
    )
    (net (code "78") (name "Net-(NPN1-C)") (class "Default")
      (node (ref "NPN1") (pin "3") (pinfunction "C_3") (pintype "unspecified"))
      (node (ref "U1") (pin "2") (pinfunction "2_2") (pintype "unspecified"))
    )
    (net (code "79") (name "Net-(NPN2-B)") (class "Default")
      (node (ref "NPN2") (pin "2") (pinfunction "B_2") (pintype "unspecified"))
      (node (ref "RA02") (pin "1") (pinfunction "1_1") (pintype "bidirectional"))
    )
    (net (code "80") (name "Net-(NPN2-C)") (class "Default")
      (node (ref "NPN2") (pin "3") (pinfunction "C_3") (pintype "unspecified"))
      (node (ref "U2") (pin "2") (pinfunction "2_2") (pintype "unspecified"))
    )
    (net (code "81") (name "Net-(NPN100-B)") (class "Default")
      (node (ref "NPN100") (pin "2") (pinfunction "B_2") (pintype "input"))
      (node (ref "R100") (pin "1") (pinfunction "1_1") (pintype "bidirectional"))
    )
    (net (code "82") (name "Net-(NPN100-C)") (class "Default")
      (node (ref "NPN100") (pin "1") (pinfunction "C_1") (pintype "input"))
      (node (ref "RELAY0-7") (pin "1") (pinfunction "1_1") (pintype "unspecified"))
    )
    (net (code "83") (name "Net-(NPN101-B)") (class "Default")
      (node (ref "NPN101") (pin "2") (pinfunction "B_2") (pintype "input"))
      (node (ref "R101") (pin "1") (pinfunction "1_1") (pintype "bidirectional"))
    )
    (net (code "84") (name "Net-(NPN101-C)") (class "Default")
      (node (ref "NPN101") (pin "1") (pinfunction "C_1") (pintype "input"))
      (node (ref "RELAY0-7") (pin "2") (pinfunction "2_2") (pintype "unspecified"))
    )
    (net (code "85") (name "Net-(NPN102-B)") (class "Default")
      (node (ref "NPN102") (pin "2") (pinfunction "B_2") (pintype "input"))
      (node (ref "R102") (pin "1") (pinfunction "1_1") (pintype "bidirectional"))
    )
    (net (code "86") (name "Net-(NPN102-C)") (class "Default")
      (node (ref "NPN102") (pin "1") (pinfunction "C_1") (pintype "input"))
      (node (ref "RELAY0-7") (pin "3") (pinfunction "3_3") (pintype "unspecified"))
    )
    (net (code "87") (name "Net-(NPN103-B)") (class "Default")
      (node (ref "NPN103") (pin "2") (pinfunction "B_2") (pintype "input"))
      (node (ref "R103") (pin "1") (pinfunction "1_1") (pintype "bidirectional"))
    )
    (net (code "88") (name "Net-(NPN103-C)") (class "Default")
      (node (ref "NPN103") (pin "1") (pinfunction "C_1") (pintype "input"))
      (node (ref "RELAY0-7") (pin "4") (pinfunction "4_4") (pintype "unspecified"))
    )
    (net (code "89") (name "Net-(NPN104-B)") (class "Default")
      (node (ref "NPN104") (pin "2") (pinfunction "B_2") (pintype "input"))
      (node (ref "R104") (pin "1") (pinfunction "1_1") (pintype "bidirectional"))
    )
    (net (code "90") (name "Net-(NPN104-C)") (class "Default")
      (node (ref "NPN104") (pin "1") (pinfunction "C_1") (pintype "input"))
      (node (ref "RELAY0-7") (pin "5") (pinfunction "5_5") (pintype "unspecified"))
    )
    (net (code "91") (name "Net-(NPN105-B)") (class "Default")
      (node (ref "NPN105") (pin "2") (pinfunction "B_2") (pintype "input"))
      (node (ref "R105") (pin "1") (pinfunction "1_1") (pintype "bidirectional"))
    )
    (net (code "92") (name "Net-(NPN105-C)") (class "Default")
      (node (ref "NPN105") (pin "1") (pinfunction "C_1") (pintype "input"))
      (node (ref "RELAY0-7") (pin "6") (pinfunction "6_6") (pintype "unspecified"))
    )
    (net (code "93") (name "Net-(NPN106-B)") (class "Default")
      (node (ref "NPN106") (pin "2") (pinfunction "B_2") (pintype "input"))
      (node (ref "R106") (pin "1") (pinfunction "1_1") (pintype "bidirectional"))
    )
    (net (code "94") (name "Net-(NPN106-C)") (class "Default")
      (node (ref "NPN106") (pin "1") (pinfunction "C_1") (pintype "input"))
      (node (ref "RELAY0-7") (pin "7") (pinfunction "7_7") (pintype "unspecified"))
    )
    (net (code "95") (name "Net-(NPN107-B)") (class "Default")
      (node (ref "NPN107") (pin "2") (pinfunction "B_2") (pintype "input"))
      (node (ref "R107") (pin "1") (pinfunction "1_1") (pintype "bidirectional"))
    )
    (net (code "96") (name "Net-(NPN107-C)") (class "Default")
      (node (ref "NPN107") (pin "1") (pinfunction "C_1") (pintype "input"))
      (node (ref "RELAY0-7") (pin "8") (pinfunction "8_8") (pintype "unspecified"))
    )
    (net (code "97") (name "Net-(NPN108-B)") (class "Default")
      (node (ref "NPN108") (pin "2") (pinfunction "B_2") (pintype "input"))
      (node (ref "R108") (pin "1") (pinfunction "1_1") (pintype "bidirectional"))
    )
    (net (code "98") (name "Net-(NPN108-C)") (class "Default")
      (node (ref "NPN108") (pin "1") (pinfunction "C_1") (pintype "input"))
      (node (ref "RELAY8-15") (pin "8") (pinfunction "8_8") (pintype "unspecified"))
    )
    (net (code "99") (name "Net-(NPN109-B)") (class "Default")
      (node (ref "NPN109") (pin "2") (pinfunction "B_2") (pintype "input"))
      (node (ref "R109") (pin "1") (pinfunction "1_1") (pintype "bidirectional"))
    )
    (net (code "100") (name "Net-(NPN109-C)") (class "Default")
      (node (ref "NPN109") (pin "1") (pinfunction "C_1") (pintype "input"))
      (node (ref "RELAY8-15") (pin "7") (pinfunction "7_7") (pintype "unspecified"))
    )
    (net (code "101") (name "Net-(NPN110-B)") (class "Default")
      (node (ref "NPN110") (pin "2") (pinfunction "B_2") (pintype "input"))
      (node (ref "R110") (pin "1") (pinfunction "1_1") (pintype "bidirectional"))
    )
    (net (code "102") (name "Net-(NPN110-C)") (class "Default")
      (node (ref "NPN110") (pin "1") (pinfunction "C_1") (pintype "input"))
      (node (ref "RELAY8-15") (pin "6") (pinfunction "6_6") (pintype "unspecified"))
    )
    (net (code "103") (name "Net-(NPN111-B)") (class "Default")
      (node (ref "NPN111") (pin "2") (pinfunction "B_2") (pintype "input"))
      (node (ref "R111") (pin "1") (pinfunction "1_1") (pintype "bidirectional"))
    )
    (net (code "104") (name "Net-(NPN111-C)") (class "Default")
      (node (ref "NPN111") (pin "1") (pinfunction "C_1") (pintype "input"))
      (node (ref "RELAY8-15") (pin "5") (pinfunction "5_5") (pintype "unspecified"))
    )
    (net (code "105") (name "Net-(NPN112-B)") (class "Default")
      (node (ref "NPN112") (pin "2") (pinfunction "B_2") (pintype "input"))
      (node (ref "R112") (pin "1") (pinfunction "1_1") (pintype "bidirectional"))
    )
    (net (code "106") (name "Net-(NPN112-C)") (class "Default")
      (node (ref "NPN112") (pin "1") (pinfunction "C_1") (pintype "input"))
      (node (ref "RELAY8-15") (pin "4") (pinfunction "4_4") (pintype "unspecified"))
    )
    (net (code "107") (name "Net-(NPN113-B)") (class "Default")
      (node (ref "NPN113") (pin "2") (pinfunction "B_2") (pintype "input"))
      (node (ref "R113") (pin "1") (pinfunction "1_1") (pintype "bidirectional"))
    )
    (net (code "108") (name "Net-(NPN113-C)") (class "Default")
      (node (ref "NPN113") (pin "1") (pinfunction "C_1") (pintype "input"))
      (node (ref "RELAY8-15") (pin "3") (pinfunction "3_3") (pintype "unspecified"))
    )
    (net (code "109") (name "Net-(NPN114-B)") (class "Default")
      (node (ref "NPN114") (pin "2") (pinfunction "B_2") (pintype "input"))
      (node (ref "R114") (pin "1") (pinfunction "1_1") (pintype "bidirectional"))
    )
    (net (code "110") (name "Net-(NPN114-C)") (class "Default")
      (node (ref "NPN114") (pin "1") (pinfunction "C_1") (pintype "input"))
      (node (ref "RELAY8-15") (pin "2") (pinfunction "2_2") (pintype "unspecified"))
    )
    (net (code "111") (name "Net-(NPN115-B)") (class "Default")
      (node (ref "NPN115") (pin "2") (pinfunction "B_2") (pintype "input"))
      (node (ref "R115") (pin "1") (pinfunction "1_1") (pintype "bidirectional"))
    )
    (net (code "112") (name "Net-(NPN115-C)") (class "Default")
      (node (ref "NPN115") (pin "1") (pinfunction "C_1") (pintype "input"))
      (node (ref "RELAY8-15") (pin "1") (pinfunction "1_1") (pintype "unspecified"))
    )
    (net (code "113") (name "Net-(R47-Pad1)") (class "Default")
      (node (ref "R47") (pin "1") (pinfunction "1_1") (pintype "bidirectional"))
      (node (ref "R49") (pin "1") (pinfunction "1_1") (pintype "bidirectional"))
      (node (ref "R50") (pin "1") (pinfunction "1_1") (pintype "bidirectional"))
    )
    (net (code "114") (name "unconnected-(A1-Pad1)") (class "Default")
      (node (ref "A1") (pin "1") (pinfunction "1_1") (pintype "unspecified"))
    )
    (net (code "115") (name "unconnected-(A1-Pad2)") (class "Default")
      (node (ref "A1") (pin "2") (pinfunction "2_2") (pintype "unspecified"))
    )
    (net (code "116") (name "unconnected-(A1-Pad3)") (class "Default")
      (node (ref "A1") (pin "3") (pinfunction "3_3") (pintype "unspecified"))
    )
    (net (code "117") (name "unconnected-(A1-Pad4)") (class "Default")
      (node (ref "A1") (pin "4") (pinfunction "4_4") (pintype "unspecified"))
    )
    (net (code "118") (name "unconnected-(A1-Pad5)") (class "Default")
      (node (ref "A1") (pin "5") (pinfunction "5_5") (pintype "unspecified"))
    )
    (net (code "119") (name "unconnected-(A1-Pad6)") (class "Default")
      (node (ref "A1") (pin "6") (pinfunction "6_6") (pintype "unspecified"))
    )
    (net (code "120") (name "unconnected-(A1-Pad7)") (class "Default")
      (node (ref "A1") (pin "7") (pinfunction "7_7") (pintype "unspecified"))
    )
    (net (code "121") (name "unconnected-(A1-Pad8)") (class "Default")
      (node (ref "A1") (pin "8") (pinfunction "8_8") (pintype "unspecified"))
    )
    (net (code "122") (name "unconnected-(A1-Pad9)") (class "Default")
      (node (ref "A1") (pin "9") (pinfunction "9_9") (pintype "unspecified"))
    )
    (net (code "123") (name "unconnected-(A1-Pad10)") (class "Default")
      (node (ref "A1") (pin "10") (pinfunction "10_10") (pintype "unspecified"))
    )
    (net (code "124") (name "unconnected-(A2-Pad1)") (class "Default")
      (node (ref "A2") (pin "1") (pinfunction "1_1") (pintype "unspecified"))
    )
    (net (code "125") (name "unconnected-(A2-Pad2)") (class "Default")
      (node (ref "A2") (pin "2") (pinfunction "2_2") (pintype "unspecified"))
    )
    (net (code "126") (name "unconnected-(A2-Pad3)") (class "Default")
      (node (ref "A2") (pin "3") (pinfunction "3_3") (pintype "unspecified"))
    )
    (net (code "127") (name "unconnected-(A2-Pad4)") (class "Default")
      (node (ref "A2") (pin "4") (pinfunction "4_4") (pintype "unspecified"))
    )
    (net (code "128") (name "unconnected-(A2-Pad5)") (class "Default")
      (node (ref "A2") (pin "5") (pinfunction "5_5") (pintype "unspecified"))
    )
    (net (code "129") (name "unconnected-(A2-Pad6)") (class "Default")
      (node (ref "A2") (pin "6") (pinfunction "6_6") (pintype "unspecified"))
    )
    (net (code "130") (name "unconnected-(A2-Pad7)") (class "Default")
      (node (ref "A2") (pin "7") (pinfunction "7_7") (pintype "unspecified"))
    )
    (net (code "131") (name "unconnected-(A2-Pad8)") (class "Default")
      (node (ref "A2") (pin "8") (pinfunction "8_8") (pintype "unspecified"))
    )
    (net (code "132") (name "unconnected-(A3-Pad1)") (class "Default")
      (node (ref "A3") (pin "1") (pinfunction "1_1") (pintype "unspecified"))
    )
    (net (code "133") (name "unconnected-(A3-Pad2)") (class "Default")
      (node (ref "A3") (pin "2") (pinfunction "2_2") (pintype "unspecified"))
    )
    (net (code "134") (name "unconnected-(A3-Pad3)") (class "Default")
      (node (ref "A3") (pin "3") (pinfunction "3_3") (pintype "unspecified"))
    )
    (net (code "135") (name "unconnected-(A3-Pad4)") (class "Default")
      (node (ref "A3") (pin "4") (pinfunction "4_4") (pintype "unspecified"))
    )
    (net (code "136") (name "unconnected-(A3-Pad5)") (class "Default")
      (node (ref "A3") (pin "5") (pinfunction "5_5") (pintype "unspecified"))
    )
    (net (code "137") (name "unconnected-(A3-Pad6)") (class "Default")
      (node (ref "A3") (pin "6") (pinfunction "6_6") (pintype "unspecified"))
    )
    (net (code "138") (name "unconnected-(A3-Pad7)") (class "Default")
      (node (ref "A3") (pin "7") (pinfunction "7_7") (pintype "unspecified"))
    )
    (net (code "139") (name "unconnected-(A3-Pad8)") (class "Default")
      (node (ref "A3") (pin "8") (pinfunction "8_8") (pintype "unspecified"))
    )
    (net (code "140") (name "unconnected-(A4-Pad1)") (class "Default")
      (node (ref "A4") (pin "1") (pinfunction "1_1") (pintype "input"))
    )
    (net (code "141") (name "unconnected-(A4-Pad2)") (class "Default")
      (node (ref "A4") (pin "2") (pinfunction "2_2") (pintype "input"))
    )
    (net (code "142") (name "unconnected-(A4-Pad3)") (class "Default")
      (node (ref "A4") (pin "3") (pinfunction "3_3") (pintype "input"))
    )
    (net (code "143") (name "unconnected-(A4-Pad4)") (class "Default")
      (node (ref "A4") (pin "4") (pinfunction "4_4") (pintype "input"))
    )
    (net (code "144") (name "unconnected-(A4-Pad5)") (class "Default")
      (node (ref "A4") (pin "5") (pinfunction "5_5") (pintype "input"))
    )
    (net (code "145") (name "unconnected-(A4-Pad6)") (class "Default")
      (node (ref "A4") (pin "6") (pinfunction "6_6") (pintype "input"))
    )
    (net (code "146") (name "unconnected-(AUDIO1-ADKEY1-Pad13)") (class "Default")
      (node (ref "AUDIO1") (pin "13") (pinfunction "ADKEY1_13") (pintype "unspecified+no_connect"))
    )
    (net (code "147") (name "unconnected-(AUDIO1-ADKEY2-Pad12)") (class "Default")
      (node (ref "AUDIO1") (pin "12") (pinfunction "ADKEY2_12") (pintype "unspecified+no_connect"))
    )
    (net (code "148") (name "unconnected-(AUDIO1-DAC_L-Pad5)") (class "Default")
      (node (ref "AUDIO1") (pin "5") (pinfunction "DAC_L_5") (pintype "unspecified+no_connect"))
    )
    (net (code "149") (name "unconnected-(AUDIO1-DAC_R-Pad4)") (class "Default")
      (node (ref "AUDIO1") (pin "4") (pinfunction "DAC_R_4") (pintype "unspecified+no_connect"))
    )
    (net (code "150") (name "unconnected-(AUDIO1-IO_1-Pad16)") (class "Default")
      (node (ref "AUDIO1") (pin "16") (pinfunction "IO_1_16") (pintype "unspecified+no_connect"))
    )
    (net (code "151") (name "unconnected-(AUDIO1-IO_2-Pad14)") (class "Default")
      (node (ref "AUDIO1") (pin "14") (pinfunction "IO_2_14") (pintype "unspecified+no_connect"))
    )
    (net (code "152") (name "unconnected-(AUDIO1-USB+-Pad11)") (class "Default")
      (node (ref "AUDIO1") (pin "11") (pinfunction "USB+_11") (pintype "unspecified+no_connect"))
    )
    (net (code "153") (name "unconnected-(AUDIO1-USB--Pad10)") (class "Default")
      (node (ref "AUDIO1") (pin "10") (pinfunction "USB-_10") (pintype "unspecified+no_connect"))
    )
    (net (code "154") (name "unconnected-(B1-Pad3.3V)") (class "Default")
      (node (ref "B1") (pin "3.3V") (pinfunction "3.3V_3.3V") (pintype "bidirectional+no_connect"))
    )
    (net (code "155") (name "unconnected-(B1-Pad5V)") (class "Default")
      (node (ref "B1") (pin "5V") (pinfunction "5V_5V") (pintype "bidirectional+no_connect"))
    )
    (net (code "156") (name "unconnected-(B1-PadA0)") (class "Default")
      (node (ref "B1") (pin "A0") (pinfunction "A0_A0") (pintype "bidirectional+no_connect"))
    )
    (net (code "157") (name "unconnected-(B1-PadA1)") (class "Default")
      (node (ref "B1") (pin "A1") (pinfunction "A1_A1") (pintype "bidirectional+no_connect"))
    )
    (net (code "158") (name "unconnected-(B1-PadA2)") (class "Default")
      (node (ref "B1") (pin "A2") (pinfunction "A2_A2") (pintype "bidirectional+no_connect"))
    )
    (net (code "159") (name "unconnected-(B1-PadAREF)") (class "Default")
      (node (ref "B1") (pin "AREF") (pinfunction "AREF_AREF") (pintype "bidirectional+no_connect"))
    )
    (net (code "160") (name "unconnected-(B1-PadD13)") (class "Default")
      (node (ref "B1") (pin "D13") (pinfunction "D13_D13") (pintype "bidirectional+no_connect"))
    )
    (net (code "161") (name "unconnected-(B1-PadIOREF)") (class "Default")
      (node (ref "B1") (pin "IOREF") (pinfunction "IOREF_IOREF") (pintype "bidirectional+no_connect"))
    )
    (net (code "162") (name "unconnected-(B1-PadRX)") (class "Default")
      (node (ref "B1") (pin "RX") (pinfunction "RX_RX") (pintype "bidirectional+no_connect"))
    )
    (net (code "163") (name "unconnected-(B1-PadSCL)") (class "Default")
      (node (ref "B1") (pin "SCL") (pinfunction "SCL_SCL") (pintype "bidirectional+no_connect"))
    )
    (net (code "164") (name "unconnected-(B1-PadSDA)") (class "Default")
      (node (ref "B1") (pin "SDA") (pinfunction "SDA_SDA") (pintype "bidirectional+no_connect"))
    )
    (net (code "165") (name "unconnected-(MCP0-GPA5-Pad26)") (class "Default")
      (node (ref "MCP0") (pin "26") (pinfunction "GPA5_26") (pintype "unspecified+no_connect"))
    )
    (net (code "166") (name "unconnected-(MCP0-GPA6-Pad27)") (class "Default")
      (node (ref "MCP0") (pin "27") (pinfunction "GPA6_27") (pintype "unspecified+no_connect"))
    )
    (net (code "167") (name "unconnected-(MCP0-GPA7-Pad28)") (class "Default")
      (node (ref "MCP0") (pin "28") (pinfunction "GPA7_28") (pintype "unspecified+no_connect"))
    )
    (net (code "168") (name "unconnected-(MCP0-GPB0-Pad1)") (class "Default")
      (node (ref "MCP0") (pin "1") (pinfunction "GPB0_1") (pintype "unspecified+no_connect"))
    )
    (net (code "169") (name "unconnected-(MCP0-GPB1-Pad2)") (class "Default")
      (node (ref "MCP0") (pin "2") (pinfunction "GPB1_2") (pintype "unspecified+no_connect"))
    )
    (net (code "170") (name "unconnected-(MCP0-GPB2-Pad3)") (class "Default")
      (node (ref "MCP0") (pin "3") (pinfunction "GPB2_3") (pintype "unspecified+no_connect"))
    )
    (net (code "171") (name "unconnected-(MCP0-GPB3-Pad4)") (class "Default")
      (node (ref "MCP0") (pin "4") (pinfunction "GPB3_4") (pintype "unspecified+no_connect"))
    )
    (net (code "172") (name "unconnected-(MCP0-GPB4-Pad5)") (class "Default")
      (node (ref "MCP0") (pin "5") (pinfunction "GPB4_5") (pintype "unspecified+no_connect"))
    )
    (net (code "173") (name "unconnected-(MCP0-GPB5-Pad6)") (class "Default")
      (node (ref "MCP0") (pin "6") (pinfunction "GPB5_6") (pintype "unspecified+no_connect"))
    )
    (net (code "174") (name "unconnected-(MCP0-GPB6-Pad7)") (class "Default")
      (node (ref "MCP0") (pin "7") (pinfunction "GPB6_7") (pintype "unspecified+no_connect"))
    )
    (net (code "175") (name "unconnected-(MCP0-GPB7-Pad8)") (class "Default")
      (node (ref "MCP0") (pin "8") (pinfunction "GPB7_8") (pintype "unspecified+no_connect"))
    )
    (net (code "176") (name "unconnected-(MCP0-INTA-Pad20)") (class "Default")
      (node (ref "MCP0") (pin "20") (pinfunction "INTA_20") (pintype "unspecified+no_connect"))
    )
    (net (code "177") (name "unconnected-(MCP0-INTB-Pad19)") (class "Default")
      (node (ref "MCP0") (pin "19") (pinfunction "INTB_19") (pintype "unspecified+no_connect"))
    )
    (net (code "178") (name "unconnected-(MCP0-NC-Pad11)") (class "Default")
      (node (ref "MCP0") (pin "11") (pinfunction "NC_11") (pintype "unspecified+no_connect"))
    )
    (net (code "179") (name "unconnected-(MCP0-NC-Pad14)") (class "Default")
      (node (ref "MCP0") (pin "14") (pinfunction "NC_14") (pintype "unspecified+no_connect"))
    )
    (net (code "180") (name "unconnected-(MCP2-INTA-Pad20)") (class "Default")
      (node (ref "MCP2") (pin "20") (pinfunction "INTA_20") (pintype "unspecified+no_connect"))
    )
    (net (code "181") (name "unconnected-(MCP2-INTB-Pad19)") (class "Default")
      (node (ref "MCP2") (pin "19") (pinfunction "INTB_19") (pintype "unspecified+no_connect"))
    )
    (net (code "182") (name "unconnected-(MCP2-NC-Pad11)") (class "Default")
      (node (ref "MCP2") (pin "11") (pinfunction "NC_11") (pintype "unspecified+no_connect"))
    )
    (net (code "183") (name "unconnected-(MCP2-NC-Pad14)") (class "Default")
      (node (ref "MCP2") (pin "14") (pinfunction "NC_14") (pintype "unspecified+no_connect"))
    )
    (net (code "184") (name "unconnected-(NAPPE-LED9-C-PadK)") (class "Default")
      (node (ref "NAPPE-LED9") (pin "K") (pinfunction "C_K") (pintype "bidirectional+no_connect"))
    )
    (net (code "185") (name "unconnected-(NAPPE-LED13-C-PadK)") (class "Default")
      (node (ref "NAPPE-LED13") (pin "K") (pinfunction "C_K") (pintype "bidirectional+no_connect"))
    )
    (net (code "186") (name "unconnected-(R51-Pad1)") (class "Default")
      (node (ref "R51") (pin "1") (pinfunction "1_1") (pintype "bidirectional+no_connect"))
    )
    (net (code "187") (name "unconnected-(SP1-1-Pad+)") (class "Default")
      (node (ref "SP1") (pin "+") (pinfunction "1_+") (pintype "bidirectional+no_connect"))
    )
    (net (code "188") (name "unconnected-(SP1-2-Pad-)") (class "Default")
      (node (ref "SP1") (pin "-") (pinfunction "2_-") (pintype "bidirectional+no_connect"))
    )
  )
)
